# ATTiny85_Breakout.net
KiCad netlist of a schematic drawn in EAGLE
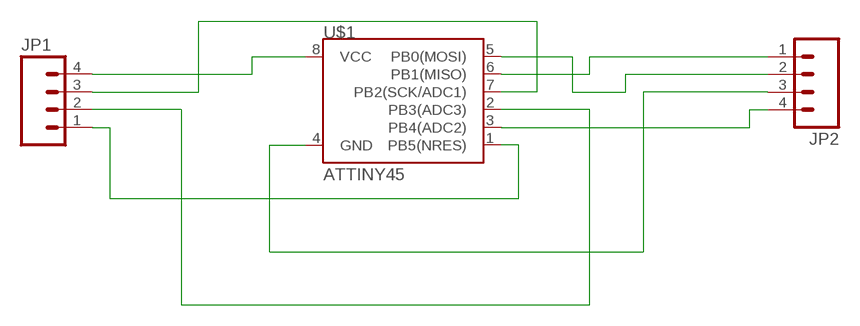
[diagram p0: schematic, sheet 1]

(export (version "E")
  (design (tool "Eeschema 10.0.6"))
  (components
    (comp (ref "JP1")
      (value "M04LOCK")
      (footprint "eagle-import:1X04_LOCK")
      (libsource (lib "eagle-import") (part "M04LOCK"))
    )
    (comp (ref "JP2")
      (value "M04LOCK")
      (footprint "eagle-import:1X04_LOCK")
      (libsource (lib "eagle-import") (part "M04LOCK"))
    )
    (comp (ref "U$1")
      (value "ATTINY45")
      (footprint "eagle-import:SO08-EIAJ")
      (libsource (lib "eagle-import") (part "ATTINY45"))
    )
  )
  (nets
    (net (code "1") (name "Net-(U$1-GND)") (class "Default")
      (node (ref "JP2") (pin "3") (pinfunction "3_3") (pintype "passive"))
      (node (ref "U$1") (pin "4") (pinfunction "GND_4") (pintype "bidirectional"))
    )
    (net (code "2") (name "Net-(U$1-PB0(MOSI))") (class "Default")
      (node (ref "JP2") (pin "2") (pinfunction "2_2") (pintype "passive"))
      (node (ref "U$1") (pin "5") (pinfunction "PB0(MOSI)_5") (pintype "bidirectional"))
    )
    (net (code "3") (name "Net-(U$1-PB1(MISO))") (class "Default")
      (node (ref "JP2") (pin "1") (pinfunction "1_1") (pintype "passive"))
      (node (ref "U$1") (pin "6") (pinfunction "PB1(MISO)_6") (pintype "bidirectional"))
    )
    (net (code "4") (name "Net-(U$1-PB2(SCK{slash}ADC1))") (class "Default")
      (node (ref "JP1") (pin "3") (pinfunction "3_3") (pintype "passive"))
      (node (ref "U$1") (pin "7") (pinfunction "PB2(SCK/ADC1)_7") (pintype "bidirectional"))
    )
    (net (code "5") (name "Net-(U$1-PB3(ADC3))") (class "Default")
      (node (ref "JP1") (pin "2") (pinfunction "2_2") (pintype "passive"))
      (node (ref "U$1") (pin "2") (pinfunction "PB3(ADC3)_2") (pintype "bidirectional"))
    )
    (net (code "6") (name "Net-(U$1-PB4(ADC2))") (class "Default")
      (node (ref "JP2") (pin "4") (pinfunction "4_4") (pintype "passive"))
      (node (ref "U$1") (pin "3") (pinfunction "PB4(ADC2)_3") (pintype "bidirectional"))
    )
    (net (code "7") (name "Net-(U$1-PB5(NRES))") (class "Default")
      (node (ref "JP1") (pin "1") (pinfunction "1_1") (pintype "passive"))
      (node (ref "U$1") (pin "1") (pinfunction "PB5(NRES)_1") (pintype "bidirectional"))
    )
    (net (code "8") (name "Net-(U$1-VCC)") (class "Default")
      (node (ref "JP1") (pin "4") (pinfunction "4_4") (pintype "passive"))
      (node (ref "U$1") (pin "8") (pinfunction "VCC_8") (pintype "bidirectional"))
    )
  )
)
